# project_pankov_power_supply.net
KiCad netlist of a schematic drawn in Altium Designer
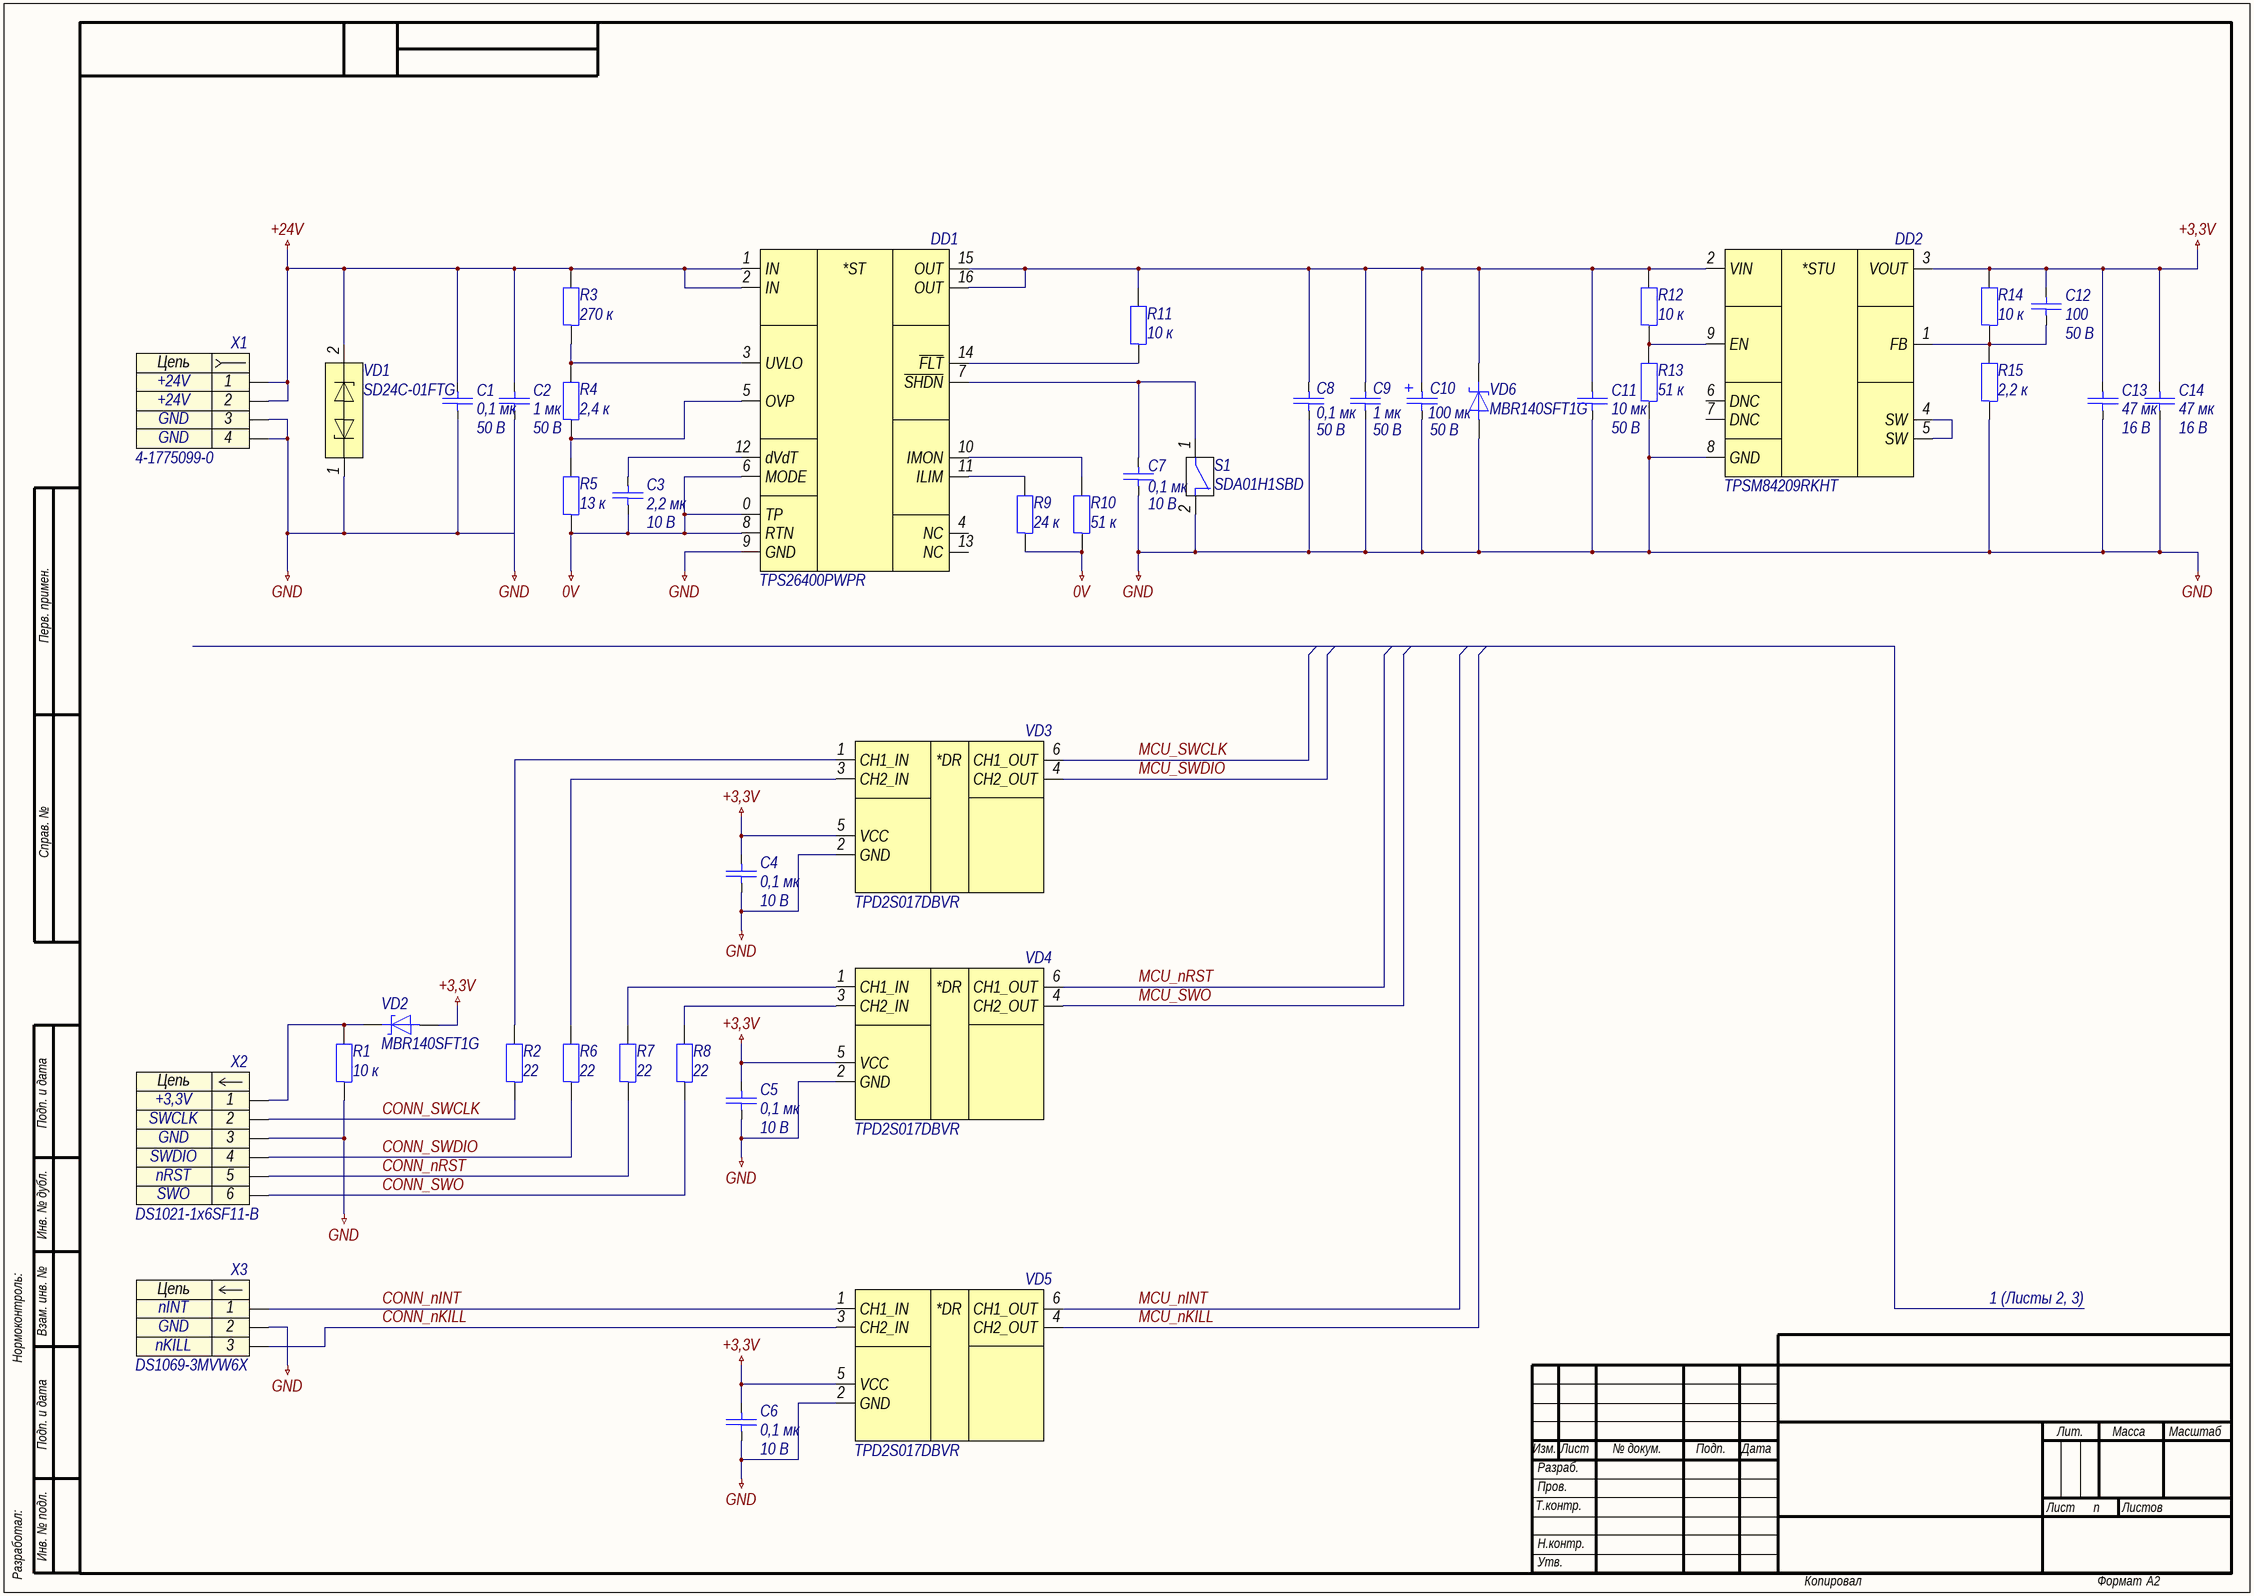
[diagram p0: project_pankov_power_supply.SchDoc]

(export (version "E")
  (design (tool "Eeschema 10.0.6"))
  (components
    (comp (ref "C1")
      (value "0,1 мк")
      (footprint "C0603")
      (description "=Описание")
      (fields (field (name "НАПРЯЖЕНИЕ") "50 В"))
      (libsource (lib "Database_Students") (part "CAPACITOR-NONPOLAR"))
    )
    (comp (ref "C2")
      (value "1 мк")
      (footprint "C0603")
      (description "=Описание")
      (fields (field (name "НАПРЯЖЕНИЕ") "50 В"))
      (libsource (lib "Database_Students") (part "CAPACITOR-NONPOLAR"))
    )
    (comp (ref "C3")
      (value "2,2 мк")
      (footprint "C0603")
      (description "=Описание")
      (fields (field (name "НАПРЯЖЕНИЕ") "10 В"))
      (libsource (lib "Database_Students") (part "CAPACITOR-NONPOLAR"))
    )
    (comp (ref "C4")
      (value "0,1 мк")
      (footprint "C0603")
      (description "=Описание")
      (fields (field (name "НАПРЯЖЕНИЕ") "10 В"))
      (libsource (lib "Database_Students") (part "CAPACITOR-NONPOLAR"))
    )
    (comp (ref "C5")
      (value "0,1 мк")
      (footprint "C0603")
      (description "=Описание")
      (fields (field (name "НАПРЯЖЕНИЕ") "10 В"))
      (libsource (lib "Database_Students") (part "CAPACITOR-NONPOLAR"))
    )
    (comp (ref "C6")
      (value "0,1 мк")
      (footprint "C0603")
      (description "=Описание")
      (fields (field (name "НАПРЯЖЕНИЕ") "10 В"))
      (libsource (lib "Database_Students") (part "CAPACITOR-NONPOLAR"))
    )
    (comp (ref "C7")
      (value "0,1 мк")
      (footprint "C0603")
      (description "=Описание")
      (fields (field (name "НАПРЯЖЕНИЕ") "10 В"))
      (libsource (lib "Database_Students") (part "CAPACITOR-NONPOLAR"))
    )
    (comp (ref "C8")
      (value "0,1 мк")
      (footprint "C0603")
      (description "=Описание")
      (fields (field (name "НАПРЯЖЕНИЕ") "50 В"))
      (libsource (lib "Database_Students") (part "CAPACITOR-NONPOLAR"))
    )
    (comp (ref "C9")
      (value "1 мк")
      (footprint "C0603")
      (description "=Описание")
      (fields (field (name "НАПРЯЖЕНИЕ") "50 В"))
      (libsource (lib "Database_Students") (part "CAPACITOR-NONPOLAR"))
    )
    (comp (ref "C10")
      (value "100 мк")
      (footprint "CAPAE-660X660X800")
      (description "=Описание")
      (fields (field (name "НАПРЯЖЕНИЕ") "50 В"))
      (libsource (lib "Database_Students") (part "CAPACITOR-POLAR"))
    )
    (comp (ref "C11")
      (value "10 мк")
      (footprint "C1206")
      (description "=Описание")
      (fields (field (name "НАПРЯЖЕНИЕ") "50 В"))
      (libsource (lib "Database_Students") (part "CAPACITOR-NONPOLAR"))
    )
    (comp (ref "C12")
      (value "100")
      (footprint "C0603")
      (description "=Описание")
      (fields (field (name "НАПРЯЖЕНИЕ") "50 В"))
      (libsource (lib "Database_Students") (part "CAPACITOR-NONPOLAR"))
    )
    (comp (ref "C13")
      (value "47 мк")
      (footprint "C1206")
      (description "=Описание")
      (fields (field (name "НАПРЯЖЕНИЕ") "16 В"))
      (libsource (lib "Database_Students") (part "CAPACITOR-NONPOLAR"))
    )
    (comp (ref "C14")
      (value "47 мк")
      (footprint "C1206")
      (description "=Описание")
      (fields (field (name "НАПРЯЖЕНИЕ") "16 В"))
      (libsource (lib "Database_Students") (part "CAPACITOR-NONPOLAR"))
    )
    (comp (ref "DD1")
      (value "TPS26400PWPR")
      (footprint "HTSSOP-16-P65-500X440X120-L63X25-T246X266")
      (description "=Описание")
      (libsource (lib "Database_Students") (part "TPS26400PWPR"))
    )
    (comp (ref "DD2")
      (value "TPSM84209RKHT")
      (footprint "QFN-FCMOD-9-P65-450X400X210")
      (description "=Описание")
      (libsource (lib "Database_Students") (part "TPSM84209RKHT"))
    )
    (comp (ref "R1")
      (value "10 к")
      (footprint "R0603")
      (description "=Описание")
      (libsource (lib "Database_Students") (part "RESISTOR-COMMON"))
    )
    (comp (ref "R2")
      (value "22")
      (footprint "R0603")
      (description "=Описание")
      (libsource (lib "Database_Students") (part "RESISTOR-COMMON"))
    )
    (comp (ref "R3")
      (value "270 к")
      (footprint "R0603")
      (description "=Описание")
      (libsource (lib "Database_Students") (part "RESISTOR-COMMON"))
    )
    (comp (ref "R4")
      (value "2,4 к")
      (footprint "R0603")
      (description "=Описание")
      (libsource (lib "Database_Students") (part "RESISTOR-COMMON"))
    )
    (comp (ref "R5")
      (value "13 к")
      (footprint "R0603")
      (description "=Описание")
      (libsource (lib "Database_Students") (part "RESISTOR-COMMON"))
    )
    (comp (ref "R6")
      (value "22")
      (footprint "R0603")
      (description "=Описание")
      (libsource (lib "Database_Students") (part "RESISTOR-COMMON"))
    )
    (comp (ref "R7")
      (value "22")
      (footprint "R0603")
      (description "=Описание")
      (libsource (lib "Database_Students") (part "RESISTOR-COMMON"))
    )
    (comp (ref "R8")
      (value "22")
      (footprint "R0603")
      (description "=Описание")
      (libsource (lib "Database_Students") (part "RESISTOR-COMMON"))
    )
    (comp (ref "R9")
      (value "24 к")
      (footprint "R0603")
      (description "=Описание")
      (libsource (lib "Database_Students") (part "RESISTOR-COMMON"))
    )
    (comp (ref "R10")
      (value "51 к")
      (footprint "R0603")
      (description "=Описание")
      (libsource (lib "Database_Students") (part "RESISTOR-COMMON"))
    )
    (comp (ref "R11")
      (value "10 к")
      (footprint "R0603")
      (description "=Описание")
      (libsource (lib "Database_Students") (part "RESISTOR-COMMON"))
    )
    (comp (ref "R12")
      (value "10 к")
      (footprint "R0603")
      (description "=Описание")
      (libsource (lib "Database_Students") (part "RESISTOR-COMMON"))
    )
    (comp (ref "R13")
      (value "51 к")
      (footprint "R0603")
      (description "=Описание")
      (libsource (lib "Database_Students") (part "RESISTOR-COMMON"))
    )
    (comp (ref "R14")
      (value "10 к")
      (footprint "R0603")
      (description "=Описание")
      (libsource (lib "Database_Students") (part "RESISTOR-COMMON"))
    )
    (comp (ref "R15")
      (value "2,2 к")
      (footprint "R0603")
      (description "=Описание")
      (libsource (lib "Database_Students") (part "RESISTOR-COMMON"))
    )
    (comp (ref "S1")
      (value "SDA01H1SBD")
      (footprint "SDA01H1SBD")
      (description "=Описание")
      (libsource (lib "Database_Students") (part "SWITCH-2C"))
    )
    (comp (ref "VD1")
      (value "SD24C-01FTG")
      (footprint "SOD-323-257X130X114")
      (description "=Описание")
      (libsource (lib "Database_Students") (part "ZENER-BI-DIRECTIONAL"))
    )
    (comp (ref "VD2")
      (value "MBR140SFT1G")
      (footprint "SOD-123FL-370X165X98")
      (description "=Описание")
      (libsource (lib "Database_Students") (part "DIODE-SCHOTTKY"))
    )
    (comp (ref "VD3")
      (value "TPD2S017DBVR")
      (footprint "SOT-23-6-P95-290X280X145")
      (description "=Описание")
      (libsource (lib "Database_Students") (part "TPD2S017DBVR"))
    )
    (comp (ref "VD4")
      (value "TPD2S017DBVR")
      (footprint "SOT-23-6-P95-290X280X145")
      (description "=Описание")
      (libsource (lib "Database_Students") (part "TPD2S017DBVR"))
    )
    (comp (ref "VD5")
      (value "TPD2S017DBVR")
      (footprint "SOT-23-6-P95-290X280X145")
      (description "=Описание")
      (libsource (lib "Database_Students") (part "TPD2S017DBVR"))
    )
    (comp (ref "VD6")
      (value "MBR140SFT1G")
      (footprint "SOD-123FL-370X165X98")
      (description "=Описание")
      (libsource (lib "Database_Students") (part "DIODE-SCHOTTKY"))
    )
    (comp (ref "X1")
      (value "4-1775099-0")
      (footprint "4-1775099-0")
      (description "=Описание")
      (libsource (lib "Database_Students") (part "HEADER-4-SCT"))
    )
    (comp (ref "X2")
      (value "DS1021-1x6SF11-B")
      (footprint "DS1021-1X6SF11-B")
      (description "=Описание")
      (libsource (lib "Database_Students") (part "HEADER-6-PLG"))
    )
    (comp (ref "X3")
      (value "DS1069-3MVW6X")
      (footprint "DS1069-3MVW6X")
      (description "=Описание")
      (libsource (lib "Database_Students") (part "HEADER-3-PLG"))
    )
  )
  (nets
    (net (code "1") (name "+3,3V") (class "Default")
      (node (ref "C12") (pin "1") (pinfunction "1_1") (pintype "passive"))
      (node (ref "C13") (pin "1") (pinfunction "1_1") (pintype "passive"))
      (node (ref "C14") (pin "1") (pinfunction "1_1") (pintype "passive"))
      (node (ref "C4") (pin "1") (pinfunction "1_1") (pintype "passive"))
      (node (ref "C5") (pin "1") (pinfunction "1_1") (pintype "passive"))
      (node (ref "C6") (pin "1") (pinfunction "1_1") (pintype "passive"))
      (node (ref "DD2") (pin "3") (pinfunction "VOUT_3") (pintype "passive"))
      (node (ref "R14") (pin "2") (pinfunction "2_2") (pintype "passive"))
      (node (ref "VD2") (pin "2") (pinfunction "2_2") (pintype "passive"))
      (node (ref "VD3") (pin "5") (pinfunction "VCC_5") (pintype "passive"))
      (node (ref "VD4") (pin "5") (pinfunction "VCC_5") (pintype "passive"))
      (node (ref "VD5") (pin "5") (pinfunction "VCC_5") (pintype "passive"))
    )
    (net (code "2") (name "+24V") (class "Default")
      (node (ref "C1") (pin "1") (pinfunction "1_1") (pintype "passive"))
      (node (ref "C2") (pin "1") (pinfunction "1_1") (pintype "passive"))
      (node (ref "DD1") (pin "1") (pinfunction "IN_1") (pintype "passive"))
      (node (ref "DD1") (pin "2") (pinfunction "IN_2") (pintype "passive"))
      (node (ref "R3") (pin "2") (pinfunction "2_2") (pintype "passive"))
      (node (ref "VD1") (pin "2") (pinfunction "2_2") (pintype "passive"))
      (node (ref "X1") (pin "1") (pinfunction "1_1") (pintype "passive"))
      (node (ref "X1") (pin "2") (pinfunction "2_2") (pintype "passive"))
    )
    (net (code "3") (name "/CONN_SWCLK") (class "Default")
      (node (ref "R2") (pin "1") (pinfunction "1_1") (pintype "passive"))
      (node (ref "X2") (pin "2") (pinfunction "2_2") (pintype "passive"))
    )
    (net (code "4") (name "/CONN_SWDIO") (class "Default")
      (node (ref "R6") (pin "1") (pinfunction "1_1") (pintype "passive"))
      (node (ref "X2") (pin "4") (pinfunction "4_4") (pintype "passive"))
    )
    (net (code "5") (name "/CONN_SWO") (class "Default")
      (node (ref "R8") (pin "1") (pinfunction "1_1") (pintype "passive"))
      (node (ref "X2") (pin "6") (pinfunction "6_6") (pintype "passive"))
    )
    (net (code "6") (name "/CONN_nINT") (class "Default")
      (node (ref "VD5") (pin "1") (pinfunction "CH1_IN_1") (pintype "passive"))
      (node (ref "X3") (pin "1") (pinfunction "1_1") (pintype "passive"))
    )
    (net (code "7") (name "/CONN_nKILL") (class "Default")
      (node (ref "VD5") (pin "3") (pinfunction "CH2_IN_3") (pintype "passive"))
      (node (ref "X3") (pin "3") (pinfunction "3_3") (pintype "passive"))
    )
    (net (code "8") (name "/CONN_nRST") (class "Default")
      (node (ref "R7") (pin "1") (pinfunction "1_1") (pintype "passive"))
      (node (ref "X2") (pin "5") (pinfunction "5_5") (pintype "passive"))
    )
    (net (code "9") (name "/MCU_SWCLK") (class "Default")
      (node (ref "VD3") (pin "6") (pinfunction "CH1_OUT_6") (pintype "passive"))
    )
    (net (code "10") (name "/MCU_SWDIO") (class "Default")
      (node (ref "VD3") (pin "4") (pinfunction "CH2_OUT_4") (pintype "passive"))
    )
    (net (code "11") (name "/MCU_SWO") (class "Default")
      (node (ref "VD4") (pin "4") (pinfunction "CH2_OUT_4") (pintype "passive"))
    )
    (net (code "12") (name "/MCU_nINT") (class "Default")
      (node (ref "VD5") (pin "6") (pinfunction "CH1_OUT_6") (pintype "passive"))
    )
    (net (code "13") (name "/MCU_nKILL") (class "Default")
      (node (ref "VD5") (pin "4") (pinfunction "CH2_OUT_4") (pintype "passive"))
    )
    (net (code "14") (name "/MCU_nRST") (class "Default")
      (node (ref "VD4") (pin "6") (pinfunction "CH1_OUT_6") (pintype "passive"))
    )
    (net (code "15") (name "0V") (class "Default")
      (node (ref "C3") (pin "2") (pinfunction "2_2") (pintype "passive"))
      (node (ref "DD1") (pin "0") (pinfunction "TP_0") (pintype "passive"))
      (node (ref "DD1") (pin "6") (pinfunction "MODE_6") (pintype "passive"))
      (node (ref "DD1") (pin "8") (pinfunction "RTN_8") (pintype "passive"))
      (node (ref "R10") (pin "1") (pinfunction "1_1") (pintype "passive"))
      (node (ref "R5") (pin "1") (pinfunction "1_1") (pintype "passive"))
      (node (ref "R9") (pin "1") (pinfunction "1_1") (pintype "passive"))
    )
    (net (code "16") (name "GND") (class "Default")
      (node (ref "C1") (pin "2") (pinfunction "2_2") (pintype "passive"))
      (node (ref "C10") (pin "2") (pinfunction "2_2") (pintype "passive"))
      (node (ref "C11") (pin "2") (pinfunction "2_2") (pintype "passive"))
      (node (ref "C13") (pin "2") (pinfunction "2_2") (pintype "passive"))
      (node (ref "C14") (pin "2") (pinfunction "2_2") (pintype "passive"))
      (node (ref "C2") (pin "2") (pinfunction "2_2") (pintype "passive"))
      (node (ref "C4") (pin "2") (pinfunction "2_2") (pintype "passive"))
      (node (ref "C5") (pin "2") (pinfunction "2_2") (pintype "passive"))
      (node (ref "C6") (pin "2") (pinfunction "2_2") (pintype "passive"))
      (node (ref "C7") (pin "2") (pinfunction "2_2") (pintype "passive"))
      (node (ref "C8") (pin "2") (pinfunction "2_2") (pintype "passive"))
      (node (ref "C9") (pin "2") (pinfunction "2_2") (pintype "passive"))
      (node (ref "DD1") (pin "9") (pinfunction "GND_9") (pintype "passive"))
      (node (ref "DD2") (pin "8") (pinfunction "GND_8") (pintype "passive"))
      (node (ref "R1") (pin "1") (pinfunction "1_1") (pintype "passive"))
      (node (ref "R13") (pin "1") (pinfunction "1_1") (pintype "passive"))
      (node (ref "R15") (pin "1") (pinfunction "1_1") (pintype "passive"))
      (node (ref "S1") (pin "2") (pinfunction "2_2") (pintype "passive"))
      (node (ref "VD1") (pin "1") (pinfunction "1_1") (pintype "passive"))
      (node (ref "VD3") (pin "2") (pinfunction "GND_2") (pintype "passive"))
      (node (ref "VD4") (pin "2") (pinfunction "GND_2") (pintype "passive"))
      (node (ref "VD5") (pin "2") (pinfunction "GND_2") (pintype "passive"))
      (node (ref "VD6") (pin "2") (pinfunction "2_2") (pintype "passive"))
      (node (ref "X1") (pin "3") (pinfunction "3_3") (pintype "passive"))
      (node (ref "X1") (pin "4") (pinfunction "4_4") (pintype "passive"))
      (node (ref "X2") (pin "3") (pinfunction "3_3") (pintype "passive"))
      (node (ref "X3") (pin "2") (pinfunction "2_2") (pintype "passive"))
    )
    (net (code "17") (name "Net-(DD1-ILIM)") (class "Default")
      (node (ref "DD1") (pin "11") (pinfunction "ILIM_11") (pintype "passive"))
      (node (ref "R9") (pin "2") (pinfunction "2_2") (pintype "passive"))
    )
    (net (code "18") (name "Net-(DD1-IMON)") (class "Default")
      (node (ref "DD1") (pin "10") (pinfunction "IMON_10") (pintype "passive"))
      (node (ref "R10") (pin "2") (pinfunction "2_2") (pintype "passive"))
    )
    (net (code "19") (name "Net-(DD1-OVP)") (class "Default")
      (node (ref "DD1") (pin "5") (pinfunction "OVP_5") (pintype "passive"))
      (node (ref "R4") (pin "1") (pinfunction "1_1") (pintype "passive"))
      (node (ref "R5") (pin "2") (pinfunction "2_2") (pintype "passive"))
    )
    (net (code "20") (name "Net-(DD1-UVLO)") (class "Default")
      (node (ref "DD1") (pin "3") (pinfunction "UVLO_3") (pintype "passive"))
      (node (ref "R3") (pin "1") (pinfunction "1_1") (pintype "passive"))
      (node (ref "R4") (pin "2") (pinfunction "2_2") (pintype "passive"))
    )
    (net (code "21") (name "Net-(DD1-dVdT)") (class "Default")
      (node (ref "C3") (pin "1") (pinfunction "1_1") (pintype "passive"))
      (node (ref "DD1") (pin "12") (pinfunction "dVdT_12") (pintype "passive"))
    )
    (net (code "22") (name "Net-(DD1-~{FLT})") (class "Default")
      (node (ref "DD1") (pin "14") (pinfunction "~{FLT}_14") (pintype "passive"))
      (node (ref "R11") (pin "1") (pinfunction "1_1") (pintype "passive"))
    )
    (net (code "23") (name "Net-(DD1-~{SHDN})") (class "Default")
      (node (ref "C7") (pin "1") (pinfunction "1_1") (pintype "passive"))
      (node (ref "DD1") (pin "7") (pinfunction "~{SHDN}_7") (pintype "passive"))
      (node (ref "S1") (pin "1") (pinfunction "1_1") (pintype "passive"))
    )
    (net (code "24") (name "Net-(DD2-EN)") (class "Default")
      (node (ref "DD2") (pin "9") (pinfunction "EN_9") (pintype "passive"))
      (node (ref "R12") (pin "1") (pinfunction "1_1") (pintype "passive"))
      (node (ref "R13") (pin "2") (pinfunction "2_2") (pintype "passive"))
    )
    (net (code "25") (name "Net-(DD2-FB)") (class "Default")
      (node (ref "C12") (pin "2") (pinfunction "2_2") (pintype "passive"))
      (node (ref "DD2") (pin "1") (pinfunction "FB_1") (pintype "passive"))
      (node (ref "R14") (pin "1") (pinfunction "1_1") (pintype "passive"))
      (node (ref "R15") (pin "2") (pinfunction "2_2") (pintype "passive"))
    )
    (net (code "26") (name "Net-(DD2-SW-Pad4)") (class "Default")
      (node (ref "DD2") (pin "4") (pinfunction "SW_4") (pintype "passive"))
      (node (ref "DD2") (pin "5") (pinfunction "SW_5") (pintype "passive"))
    )
    (net (code "27") (name "Net-(DD2-VIN)") (class "Default")
      (node (ref "C10") (pin "1") (pinfunction "1_1") (pintype "passive"))
      (node (ref "C11") (pin "1") (pinfunction "1_1") (pintype "passive"))
      (node (ref "C8") (pin "1") (pinfunction "1_1") (pintype "passive"))
      (node (ref "C9") (pin "1") (pinfunction "1_1") (pintype "passive"))
      (node (ref "DD1") (pin "15") (pinfunction "OUT_15") (pintype "passive"))
      (node (ref "DD1") (pin "16") (pinfunction "OUT_16") (pintype "passive"))
      (node (ref "DD2") (pin "2") (pinfunction "VIN_2") (pintype "passive"))
      (node (ref "R11") (pin "2") (pinfunction "2_2") (pintype "passive"))
      (node (ref "R12") (pin "2") (pinfunction "2_2") (pintype "passive"))
      (node (ref "VD6") (pin "1") (pinfunction "1_1") (pintype "passive"))
    )
    (net (code "28") (name "Net-(R1-Pad2)") (class "Default")
      (node (ref "R1") (pin "2") (pinfunction "2_2") (pintype "passive"))
      (node (ref "VD2") (pin "1") (pinfunction "1_1") (pintype "passive"))
      (node (ref "X2") (pin "1") (pinfunction "1_1") (pintype "passive"))
    )
    (net (code "29") (name "Net-(VD3-CH1_IN)") (class "Default")
      (node (ref "R2") (pin "2") (pinfunction "2_2") (pintype "passive"))
      (node (ref "VD3") (pin "1") (pinfunction "CH1_IN_1") (pintype "passive"))
    )
    (net (code "30") (name "Net-(VD3-CH2_IN)") (class "Default")
      (node (ref "R6") (pin "2") (pinfunction "2_2") (pintype "passive"))
      (node (ref "VD3") (pin "3") (pinfunction "CH2_IN_3") (pintype "passive"))
    )
    (net (code "31") (name "Net-(VD4-CH1_IN)") (class "Default")
      (node (ref "R7") (pin "2") (pinfunction "2_2") (pintype "passive"))
      (node (ref "VD4") (pin "1") (pinfunction "CH1_IN_1") (pintype "passive"))
    )
    (net (code "32") (name "Net-(VD4-CH2_IN)") (class "Default")
      (node (ref "R8") (pin "2") (pinfunction "2_2") (pintype "passive"))
      (node (ref "VD4") (pin "3") (pinfunction "CH2_IN_3") (pintype "passive"))
    )
    (net (code "33") (name "unconnected-(DD1-NC-Pad4)") (class "Default")
      (node (ref "DD1") (pin "4") (pinfunction "NC_4") (pintype "passive"))
    )
    (net (code "34") (name "unconnected-(DD1-NC-Pad13)") (class "Default")
      (node (ref "DD1") (pin "13") (pinfunction "NC_13") (pintype "passive"))
    )
    (net (code "35") (name "unconnected-(DD2-DNC-Pad6)") (class "Default")
      (node (ref "DD2") (pin "6") (pinfunction "DNC_6") (pintype "passive"))
    )
    (net (code "36") (name "unconnected-(DD2-DNC-Pad7)") (class "Default")
      (node (ref "DD2") (pin "7") (pinfunction "DNC_7") (pintype "passive"))
    )
  )
)
